# ManitoBoardv_7_1.net
KiCad netlist of a schematic drawn in EAGLE
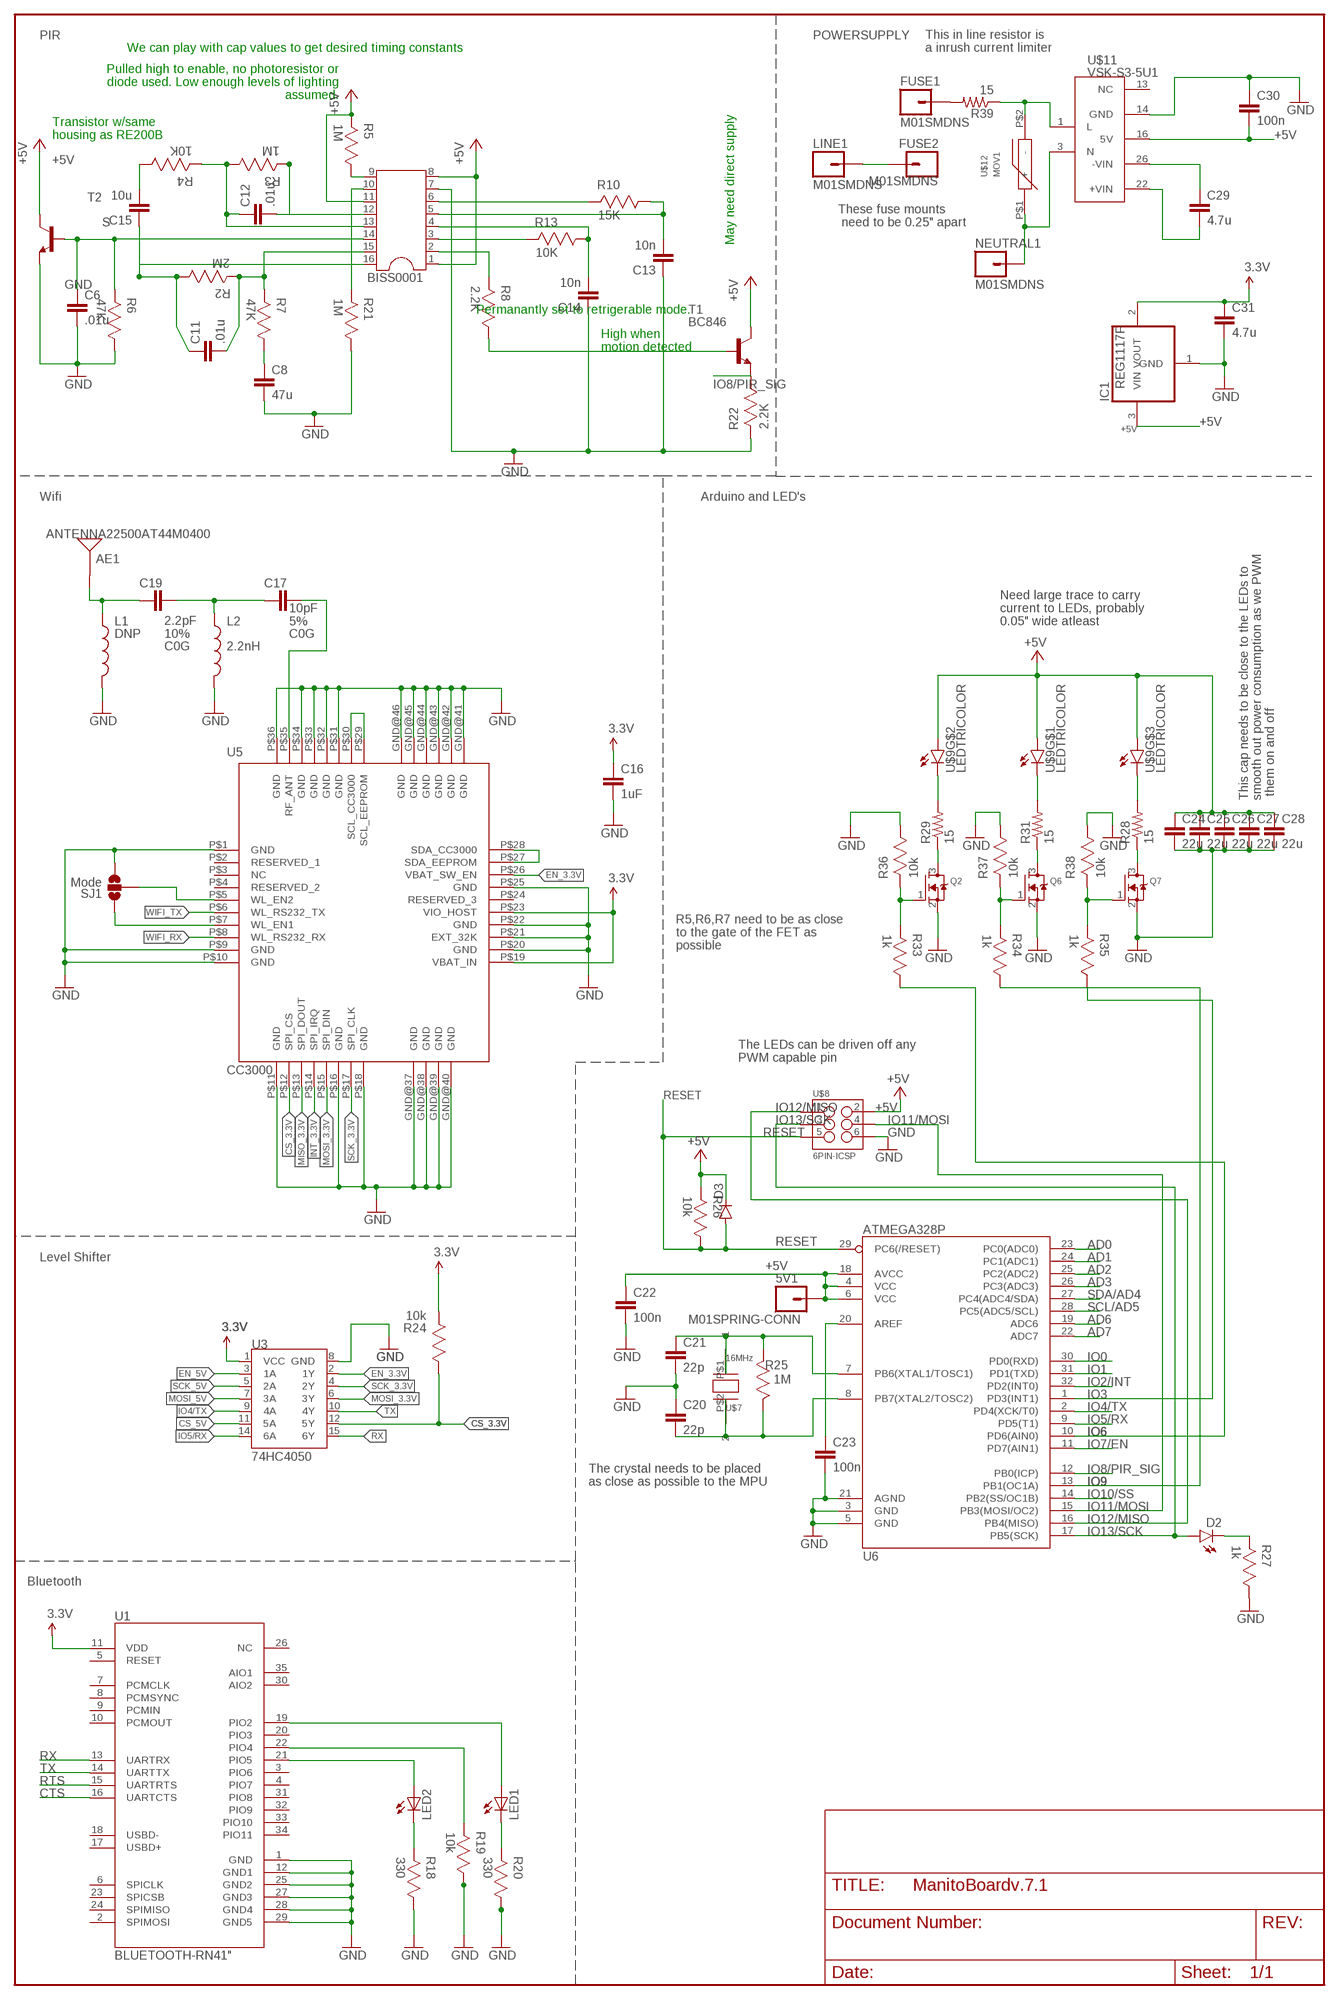
[diagram p0: schematic, sheet 1]

(export (version "E")
  (design (tool "Eeschema 10.0.6"))
  (components
    (comp (ref "5V1")
      (value "M01SPRING-CONN")
      (footprint "eagle-import:SPRING-CONNECTOR")
      (libsource (lib "eagle-import") (part "M01SPRING-CONN"))
    )
    (comp (ref "AE1")
      (value "ANTENNA22500AT44M0400")
      (footprint "eagle-import:ANTENNA-CHIP_2500AT44M0400")
      (libsource (lib "eagle-import") (part "ANTENNA22500AT44M0400"))
    )
    (comp (ref "BISS0001")
      (value "DIL16S")
      (footprint "eagle-import:SOCKET-16")
      (libsource (lib "eagle-import") (part "DIL16S"))
    )
    (comp (ref "C6")
      (value ".01u")
      (footprint "eagle-import:0805")
      (libsource (lib "eagle-import") (part "CAP0805"))
    )
    (comp (ref "C8")
      (value "47u")
      (footprint "eagle-import:0805")
      (libsource (lib "eagle-import") (part "CAP0805"))
    )
    (comp (ref "C11")
      (value ".01u")
      (footprint "eagle-import:0805")
      (libsource (lib "eagle-import") (part "CAP0805"))
    )
    (comp (ref "C12")
      (value ".01u")
      (footprint "eagle-import:0805")
      (libsource (lib "eagle-import") (part "CAP0805"))
    )
    (comp (ref "C13")
      (value "10n")
      (footprint "eagle-import:0805")
      (libsource (lib "eagle-import") (part "CAP0805"))
    )
    (comp (ref "C14")
      (value "10n")
      (footprint "eagle-import:0805")
      (libsource (lib "eagle-import") (part "CAP0805"))
    )
    (comp (ref "C15")
      (value "10u")
      (footprint "eagle-import:0805")
      (libsource (lib "eagle-import") (part "CAP0805"))
    )
    (comp (ref "C16")
      (value "1uF")
      (footprint "eagle-import:0805")
      (libsource (lib "eagle-import") (part "SparkFun-Capacitors_CAP0805"))
    )
    (comp (ref "C17")
      (value "10pF")
      (footprint "eagle-import:0603-CAP")
      (fields (field (name "COEFF") "C0G") (field (name "TOL") "5%"))
      (libsource (lib "eagle-import") (part "SparkFun-Capacitors_CAP0603-CAP"))
    )
    (comp (ref "C19")
      (value "2.2pF")
      (footprint "eagle-import:0603-CAP")
      (fields (field (name "COEFF") "C0G") (field (name "TOL") "10%"))
      (libsource (lib "eagle-import") (part "SparkFun-Capacitors_CAP0603-CAP"))
    )
    (comp (ref "C20")
      (value "22p")
      (footprint "eagle-import:0603-CAP")
      (libsource (lib "eagle-import") (part "CAP0603-CAP"))
    )
    (comp (ref "C21")
      (value "22p")
      (footprint "eagle-import:0603-CAP")
      (libsource (lib "eagle-import") (part "CAP0603-CAP"))
    )
    (comp (ref "C22")
      (value "100n")
      (footprint "eagle-import:0603-CAP")
      (libsource (lib "eagle-import") (part "CAP0603-CAP"))
    )
    (comp (ref "C23")
      (value "100n")
      (footprint "eagle-import:0603-CAP")
      (libsource (lib "eagle-import") (part "CAP0603-CAP"))
    )
    (comp (ref "C24")
      (value "22u")
      (footprint "eagle-import:0603-CAP")
      (libsource (lib "eagle-import") (part "CAP0603-CAP"))
    )
    (comp (ref "C25")
      (value "22u")
      (footprint "eagle-import:0603-CAP")
      (libsource (lib "eagle-import") (part "CAP0603-CAP"))
    )
    (comp (ref "C26")
      (value "22u")
      (footprint "eagle-import:0603-CAP")
      (libsource (lib "eagle-import") (part "CAP0603-CAP"))
    )
    (comp (ref "C27")
      (value "22u")
      (footprint "eagle-import:0603-CAP")
      (libsource (lib "eagle-import") (part "CAP0603-CAP"))
    )
    (comp (ref "C28")
      (value "22u")
      (footprint "eagle-import:0603-CAP")
      (libsource (lib "eagle-import") (part "CAP0603-CAP"))
    )
    (comp (ref "C29")
      (value "4.7u")
      (footprint "eagle-import:0603-CAP")
      (libsource (lib "eagle-import") (part "CAP0603-CAP"))
    )
    (comp (ref "C30")
      (value "100n")
      (footprint "eagle-import:0603-CAP")
      (libsource (lib "eagle-import") (part "CAP0603-CAP"))
    )
    (comp (ref "C31")
      (value "4.7u")
      (footprint "eagle-import:0603-CAP")
      (libsource (lib "eagle-import") (part "CAP0603-CAP"))
    )
    (comp (ref "D2")
      (value "LED-YELLOW0603")
      (footprint "eagle-import:LED-0603")
      (libsource (lib "eagle-import") (part "LED-YELLOW0603"))
    )
    (comp (ref "D3")
      (value "DIODE1N4148")
      (footprint "eagle-import:DIODE-1N4148")
      (libsource (lib "eagle-import") (part "DIODE1N4148"))
    )
    (comp (ref "FUSE1")
      (value "M01SMDNS")
      (footprint "eagle-import:1X01NS")
      (libsource (lib "eagle-import") (part "M01SMDNS"))
    )
    (comp (ref "FUSE2")
      (value "M01SMDNS")
      (footprint "eagle-import:1X01NS")
      (libsource (lib "eagle-import") (part "M01SMDNS"))
    )
    (comp (ref "IC1")
      (value "REG1117F")
      (footprint "eagle-import:DD-3")
      (fields (field (name "MF") "TEXAS INSTRUMENTS") (field (name "MPN") "REG1117FAKTTT"))
      (libsource (lib "eagle-import") (part "REG1117F"))
    )
    (comp (ref "L1")
      (value "DNP")
      (footprint "eagle-import:0603")
      (libsource (lib "eagle-import") (part "INDUCTOR0603"))
    )
    (comp (ref "L2")
      (value "2.2nH")
      (footprint "eagle-import:0603")
      (libsource (lib "eagle-import") (part "INDUCTOR0603"))
    )
    (comp (ref "LED1")
      (value "LED_ESML0603")
      (footprint "eagle-import:LED_SML0603")
      (libsource (lib "eagle-import") (part "LED_ESML0603"))
    )
    (comp (ref "LED2")
      (value "LED_ESML0603")
      (footprint "eagle-import:LED_SML0603")
      (libsource (lib "eagle-import") (part "LED_ESML0603"))
    )
    (comp (ref "LINE1")
      (value "M01SMDNS")
      (footprint "eagle-import:1X01NS")
      (libsource (lib "eagle-import") (part "M01SMDNS"))
    )
    (comp (ref "NEUTRAL1")
      (value "M01SMDNS")
      (footprint "eagle-import:1X01NS")
      (libsource (lib "eagle-import") (part "M01SMDNS"))
    )
    (comp (ref "Q2")
      (value "MOSFET-NREFLOW")
      (footprint "eagle-import:SOT23")
      (libsource (lib "eagle-import") (part "MOSFET-NREFLOW"))
    )
    (comp (ref "Q6")
      (value "MOSFET-NREFLOW")
      (footprint "eagle-import:SOT23")
      (libsource (lib "eagle-import") (part "MOSFET-NREFLOW"))
    )
    (comp (ref "Q7")
      (value "MOSFET-NREFLOW")
      (footprint "eagle-import:SOT23")
      (libsource (lib "eagle-import") (part "MOSFET-NREFLOW"))
    )
    (comp (ref "R2")
      (value "2M")
      (footprint "eagle-import:0603RESISTOR")
      (fields (field (name "MPN") "CRCW06031K21FKEA") (field (name "TOLERANCE") "± 1.0 %"))
      (libsource (lib "eagle-import") (part "0603RESISTOR1"))
    )
    (comp (ref "R3")
      (value "1M")
      (footprint "eagle-import:0603RESISTOR")
      (fields (field (name "MPN") "CRCW06031K21FKEA") (field (name "TOLERANCE") "± 1.0 %"))
      (libsource (lib "eagle-import") (part "0603RESISTOR1"))
    )
    (comp (ref "R4")
      (value "10K")
      (footprint "eagle-import:0603RESISTOR")
      (fields (field (name "MPN") "CRCW06031K21FKEA") (field (name "TOLERANCE") "± 1.0 %"))
      (libsource (lib "eagle-import") (part "0603RESISTOR1"))
    )
    (comp (ref "R5")
      (value "1M")
      (footprint "eagle-import:0603RESISTOR")
      (fields (field (name "MPN") "CRCW06031K21FKEA") (field (name "TOLERANCE") "± 1.0 %"))
      (libsource (lib "eagle-import") (part "0603RESISTOR1"))
    )
    (comp (ref "R6")
      (value "47K")
      (footprint "eagle-import:0603RESISTOR")
      (fields (field (name "MPN") "CRCW06031K21FKEA") (field (name "TOLERANCE") "± 1.0 %"))
      (libsource (lib "eagle-import") (part "0603RESISTOR1"))
    )
    (comp (ref "R7")
      (value "47K")
      (footprint "eagle-import:0603RESISTOR")
      (fields (field (name "MPN") "CRCW06031K21FKEA") (field (name "TOLERANCE") "± 1.0 %"))
      (libsource (lib "eagle-import") (part "0603RESISTOR1"))
    )
    (comp (ref "R8")
      (value "2.2K")
      (footprint "eagle-import:0603RESISTOR")
      (fields (field (name "MPN") "CRCW06031K21FKEA") (field (name "TOLERANCE") "± 1.0 %"))
      (libsource (lib "eagle-import") (part "0603RESISTOR1"))
    )
    (comp (ref "R10")
      (value "15K")
      (footprint "eagle-import:0603RESISTOR")
      (fields (field (name "MPN") "CRCW06031K21FKEA") (field (name "TOLERANCE") "± 1.0 %"))
      (libsource (lib "eagle-import") (part "0603RESISTOR1"))
    )
    (comp (ref "R13")
      (value "10K")
      (footprint "eagle-import:0603RESISTOR")
      (fields (field (name "MPN") "CRCW06031K21FKEA") (field (name "TOLERANCE") "± 1.0 %"))
      (libsource (lib "eagle-import") (part "0603RESISTOR1"))
    )
    (comp (ref "R18")
      (value "330")
      (footprint "eagle-import:0603RESISTOR")
      (fields (field (name "MPN") "CRCW06031K21FKEA") (field (name "TOLERANCE") "± 1.0 %"))
      (libsource (lib "eagle-import") (part "0603RESISTOR1"))
    )
    (comp (ref "R19")
      (value "10k")
      (footprint "eagle-import:0603RESISTOR")
      (fields (field (name "MPN") "CRCW06031K21FKEA") (field (name "TOLERANCE") "± 1.0 %"))
      (libsource (lib "eagle-import") (part "0603RESISTOR1"))
    )
    (comp (ref "R20")
      (value "330")
      (footprint "eagle-import:0603RESISTOR")
      (fields (field (name "MPN") "CRCW06031K21FKEA") (field (name "TOLERANCE") "± 1.0 %"))
      (libsource (lib "eagle-import") (part "0603RESISTOR1"))
    )
    (comp (ref "R21")
      (value "1M")
      (footprint "eagle-import:0603RESISTOR")
      (fields (field (name "MPN") "CRCW06031K21FKEA") (field (name "TOLERANCE") "± 1.0 %"))
      (libsource (lib "eagle-import") (part "0603RESISTOR1"))
    )
    (comp (ref "R22")
      (value "2.2K")
      (footprint "eagle-import:0603RESISTOR")
      (fields (field (name "MPN") "CRCW06031K21FKEA") (field (name "TOLERANCE") "± 1.0 %"))
      (libsource (lib "eagle-import") (part "0603RESISTOR1"))
    )
    (comp (ref "R24")
      (value "10k")
      (footprint "eagle-import:0603RESISTOR")
      (fields (field (name "MPN") "CRCW06031K21FKEA") (field (name "TOLERANCE") "± 1.0 %"))
      (libsource (lib "eagle-import") (part "0603RESISTOR1"))
    )
    (comp (ref "R25")
      (value "1M")
      (footprint "eagle-import:0603RESISTOR")
      (fields (field (name "MPN") "CRCW06031K21FKEA") (field (name "TOLERANCE") "± 1.0 %"))
      (libsource (lib "eagle-import") (part "0603RESISTOR1"))
    )
    (comp (ref "R26")
      (value "10k")
      (footprint "eagle-import:0603RESISTOR")
      (fields (field (name "MPN") "CRCW06031K21FKEA") (field (name "TOLERANCE") "± 1.0 %"))
      (libsource (lib "eagle-import") (part "0603RESISTOR1"))
    )
    (comp (ref "R27")
      (value "1k")
      (footprint "eagle-import:0603RESISTOR")
      (fields (field (name "MPN") "CRCW06031K21FKEA") (field (name "TOLERANCE") "± 1.0 %"))
      (libsource (lib "eagle-import") (part "0603RESISTOR1"))
    )
    (comp (ref "R28")
      (value "15")
      (footprint "eagle-import:AXIAL-0.6")
      (libsource (lib "eagle-import") (part "RESISTORPTH-1W"))
    )
    (comp (ref "R29")
      (value "15")
      (footprint "eagle-import:AXIAL-0.6")
      (libsource (lib "eagle-import") (part "RESISTORPTH-1W"))
    )
    (comp (ref "R31")
      (value "15")
      (footprint "eagle-import:AXIAL-0.6")
      (libsource (lib "eagle-import") (part "RESISTORPTH-1W"))
    )
    (comp (ref "R33")
      (value "1k")
      (footprint "eagle-import:0603RESISTOR")
      (fields (field (name "MPN") "CRCW06031K21FKEA") (field (name "TOLERANCE") "± 1.0 %"))
      (libsource (lib "eagle-import") (part "0603RESISTOR1"))
    )
    (comp (ref "R34")
      (value "1k")
      (footprint "eagle-import:0603RESISTOR")
      (fields (field (name "MPN") "CRCW06031K21FKEA") (field (name "TOLERANCE") "± 1.0 %"))
      (libsource (lib "eagle-import") (part "0603RESISTOR1"))
    )
    (comp (ref "R35")
      (value "1k")
      (footprint "eagle-import:0603RESISTOR")
      (fields (field (name "MPN") "CRCW06031K21FKEA") (field (name "TOLERANCE") "± 1.0 %"))
      (libsource (lib "eagle-import") (part "0603RESISTOR1"))
    )
    (comp (ref "R36")
      (value "10k")
      (footprint "eagle-import:0603RESISTOR")
      (fields (field (name "MPN") "CRCW06031K21FKEA") (field (name "TOLERANCE") "± 1.0 %"))
      (libsource (lib "eagle-import") (part "0603RESISTOR1"))
    )
    (comp (ref "R37")
      (value "10k")
      (footprint "eagle-import:0603RESISTOR")
      (fields (field (name "MPN") "CRCW06031K21FKEA") (field (name "TOLERANCE") "± 1.0 %"))
      (libsource (lib "eagle-import") (part "0603RESISTOR1"))
    )
    (comp (ref "R38")
      (value "10k")
      (footprint "eagle-import:0603RESISTOR")
      (fields (field (name "MPN") "CRCW06031K21FKEA") (field (name "TOLERANCE") "± 1.0 %"))
      (libsource (lib "eagle-import") (part "0603RESISTOR1"))
    )
    (comp (ref "R39")
      (value "15")
      (footprint "eagle-import:AXIAL-0.6")
      (libsource (lib "eagle-import") (part "RESISTORPTH-1W"))
    )
    (comp (ref "SJ1")
      (value "Mode")
      (footprint "eagle-import:SJ_3_PASTE1&2")
      (libsource (lib "eagle-import") (part "SOLDERJUMPER_2WAYPASTE1&2"))
    )
    (comp (ref "T1")
      (value "BC846")
      (footprint "eagle-import:SOT23")
      (libsource (lib "eagle-import") (part "BC846"))
    )
    (comp (ref "T2")
      (value "-NPN-TO5")
      (footprint "eagle-import:TO5")
      (libsource (lib "eagle-import") (part "-NPN-TO5"))
    )
    (comp (ref "U$7")
      (value "16MHz")
      (footprint "eagle-import:SMDCRYSTAL")
      (libsource (lib "eagle-import") (part "SMDCRYSTAL"))
    )
    (comp (ref "U$8")
      (value "6PIN-ICSP")
      (footprint "eagle-import:2X3-ICSP")
      (libsource (lib "eagle-import") (part "6PIN-ICSP"))
    )
    (comp (ref "U$9")
      (value "LEDTRICOLOR")
      (footprint "eagle-import:TRICOLORLED")
      (libsource (lib "eagle-import") (part "LEDTRICOLOR"))
    )
    (comp (ref "U$11")
      (value "VSK-S3-5U1")
      (footprint "eagle-import:VSK-S3-DCAC")
      (libsource (lib "eagle-import") (part "VSK-S3-5U1"))
    )
    (comp (ref "U$12")
      (value "MOV1")
      (footprint "eagle-import:MOV")
      (libsource (lib "eagle-import") (part "MOV1"))
    )
    (comp (ref "U1")
      (value "BLUETOOTH-RN41\"")
      (footprint "eagle-import:RN41")
      (libsource (lib "eagle-import") (part "BLUETOOTH-RN41{dblquote}"))
    )
    (comp (ref "U3")
      (value "74HC4050")
      (footprint "eagle-import:SO016")
      (libsource (lib "eagle-import") (part "HEX_CONVERTER"))
    )
    (comp (ref "U5")
      (value "CC3000")
      (footprint "eagle-import:QFN-46_CC3000")
      (libsource (lib "eagle-import") (part "CC3000"))
    )
    (comp (ref "U6")
      (value "ATMEGA328P")
      (footprint "eagle-import:TQFP32-08")
      (libsource (lib "eagle-import") (part "ATMEGA328_SMT"))
    )
  )
  (nets
    (net (code "1") (name "+5V") (class "Default")
      (node (ref "5V1") (pin "P$2") (pinfunction "1_P$2") (pintype "passive"))
      (node (ref "BISS0001") (pin "1") (pinfunction "1_1") (pintype "passive"))
      (node (ref "BISS0001") (pin "11") (pinfunction "11_11") (pintype "passive"))
      (node (ref "BISS0001") (pin "8") (pinfunction "8_8") (pintype "passive"))
      (node (ref "C22") (pin "1") (pinfunction "1_1") (pintype "passive"))
      (node (ref "C24") (pin "1") (pinfunction "1_1") (pintype "passive"))
      (node (ref "C25") (pin "1") (pinfunction "1_1") (pintype "passive"))
      (node (ref "C26") (pin "1") (pinfunction "1_1") (pintype "passive"))
      (node (ref "C27") (pin "1") (pinfunction "1_1") (pintype "passive"))
      (node (ref "C28") (pin "1") (pinfunction "1_1") (pintype "passive"))
      (node (ref "C30") (pin "2") (pinfunction "2_2") (pintype "passive"))
      (node (ref "D3") (pin "C") (pinfunction "C_C") (pintype "passive"))
      (node (ref "IC1") (pin "3") (pinfunction "VIN_3") (pintype "input"))
      (node (ref "R26") (pin "2") (pinfunction "2_2") (pintype "passive"))
      (node (ref "R5") (pin "2") (pinfunction "2_2") (pintype "passive"))
      (node (ref "T1") (pin "3") (pinfunction "C_3") (pintype "passive"))
      (node (ref "T2") (pin "3") (pinfunction "C_3") (pintype "passive"))
      (node (ref "U$11") (pin "16") (pinfunction "5V_16") (pintype "bidirectional"))
      (node (ref "U$8") (pin "2") (pinfunction "+5V_2") (pintype "power_in"))
      (node (ref "U$9") (pin "A1") (pinfunction "A_A1") (pintype "passive"))
      (node (ref "U$9") (pin "A2") (pinfunction "A_A2") (pintype "passive"))
      (node (ref "U$9") (pin "A3") (pinfunction "A_A3") (pintype "passive"))
      (node (ref "U6") (pin "18") (pinfunction "AVCC_18") (pintype "bidirectional"))
      (node (ref "U6") (pin "4") (pinfunction "VCC_4") (pintype "bidirectional"))
      (node (ref "U6") (pin "6") (pinfunction "VCC_6") (pintype "bidirectional"))
    )
    (net (code "2") (name "/AD0") (class "Default")
      (node (ref "U6") (pin "23") (pinfunction "PC0(ADC0)_23") (pintype "bidirectional"))
    )
    (net (code "3") (name "/AD1") (class "Default")
      (node (ref "U6") (pin "24") (pinfunction "PC1(ADC1)_24") (pintype "bidirectional"))
    )
    (net (code "4") (name "/AD2") (class "Default")
      (node (ref "U6") (pin "25") (pinfunction "PC2(ADC2)_25") (pintype "bidirectional"))
    )
    (net (code "5") (name "/AD3") (class "Default")
      (node (ref "U6") (pin "26") (pinfunction "PC3(ADC3)_26") (pintype "bidirectional"))
    )
    (net (code "6") (name "/AD6") (class "Default")
      (node (ref "U6") (pin "19") (pinfunction "ADC6_19") (pintype "bidirectional"))
    )
    (net (code "7") (name "/AD7") (class "Default")
      (node (ref "U6") (pin "22") (pinfunction "ADC7_22") (pintype "bidirectional"))
    )
    (net (code "8") (name "/CTS") (class "Default")
      (node (ref "U1") (pin "16") (pinfunction "UARTCTS_16") (pintype "bidirectional"))
    )
    (net (code "9") (name "/IO0") (class "Default")
      (node (ref "U6") (pin "30") (pinfunction "PD0(RXD)_30") (pintype "bidirectional"))
    )
    (net (code "10") (name "/IO1") (class "Default")
      (node (ref "U6") (pin "31") (pinfunction "PD1(TXD)_31") (pintype "bidirectional"))
    )
    (net (code "11") (name "/IO2{slash}INT") (class "Default")
      (node (ref "U6") (pin "32") (pinfunction "PD2(INT0)_32") (pintype "bidirectional"))
    )
    (net (code "12") (name "/IO3") (class "Default")
      (node (ref "R35") (pin "1") (pinfunction "1_1") (pintype "passive"))
      (node (ref "U6") (pin "1") (pinfunction "PD3(INT1)_1") (pintype "bidirectional"))
    )
    (net (code "13") (name "/IO6") (class "Default")
      (node (ref "R33") (pin "1") (pinfunction "1_1") (pintype "passive"))
      (node (ref "U6") (pin "10") (pinfunction "PD6(AIN0)_10") (pintype "bidirectional"))
    )
    (net (code "14") (name "/IO7{slash}EN") (class "Default")
      (node (ref "U6") (pin "11") (pinfunction "PD7(AIN1)_11") (pintype "bidirectional"))
    )
    (net (code "15") (name "/IO8{slash}PIR_SIG") (class "Default")
      (node (ref "R22") (pin "1") (pinfunction "1_1") (pintype "passive"))
      (node (ref "T1") (pin "2") (pinfunction "E_2") (pintype "passive"))
      (node (ref "U6") (pin "12") (pinfunction "PB0(ICP)_12") (pintype "bidirectional"))
    )
    (net (code "16") (name "/IO9") (class "Default")
      (node (ref "R34") (pin "1") (pinfunction "1_1") (pintype "passive"))
      (node (ref "U6") (pin "13") (pinfunction "PB1(OC1A)_13") (pintype "bidirectional"))
    )
    (net (code "17") (name "/IO10{slash}SS") (class "Default")
      (node (ref "U6") (pin "14") (pinfunction "PB2(SS/OC1B)_14") (pintype "bidirectional"))
    )
    (net (code "18") (name "/IO11{slash}MOSI") (class "Default")
      (node (ref "U$8") (pin "4") (pinfunction "MOSI_4") (pintype "bidirectional"))
      (node (ref "U6") (pin "15") (pinfunction "PB3(MOSI/OC2)_15") (pintype "bidirectional"))
    )
    (net (code "19") (name "/IO12{slash}MISO") (class "Default")
      (node (ref "U$8") (pin "1") (pinfunction "MISO_1") (pintype "bidirectional"))
      (node (ref "U6") (pin "16") (pinfunction "PB4(MISO)_16") (pintype "bidirectional"))
    )
    (net (code "20") (name "/IO13{slash}SCK") (class "Default")
      (node (ref "D2") (pin "A") (pinfunction "A_A") (pintype "passive"))
      (node (ref "U$8") (pin "3") (pinfunction "SCK_3") (pintype "bidirectional"))
      (node (ref "U6") (pin "17") (pinfunction "PB5(SCK)_17") (pintype "bidirectional"))
    )
    (net (code "22") (name "/RESET") (class "Default")
      (node (ref "D3") (pin "A") (pinfunction "A_A") (pintype "passive"))
      (node (ref "R26") (pin "1") (pinfunction "1_1") (pintype "passive"))
      (node (ref "U$8") (pin "5") (pinfunction "RESET_5") (pintype "bidirectional"))
      (node (ref "U6") (pin "29") (pinfunction "PC6(/RESET)_29") (pintype "bidirectional"))
    )
    (net (code "23") (name "/RTS") (class "Default")
      (node (ref "U1") (pin "15") (pinfunction "UARTRTS_15") (pintype "bidirectional"))
    )
    (net (code "24") (name "/S") (class "Default")
      (node (ref "BISS0001") (pin "14") (pinfunction "14_14") (pintype "passive"))
      (node (ref "C6") (pin "1") (pinfunction "1_1") (pintype "passive"))
      (node (ref "R6") (pin "2") (pinfunction "2_2") (pintype "passive"))
      (node (ref "T2") (pin "2") (pinfunction "B_2") (pintype "passive"))
    )
    (net (code "25") (name "/SCL{slash}AD5") (class "Default")
      (node (ref "U6") (pin "28") (pinfunction "PC5(ADC5/SCL)_28") (pintype "bidirectional"))
    )
    (net (code "26") (name "/SDA{slash}AD4") (class "Default")
      (node (ref "U6") (pin "27") (pinfunction "PC4(ADC4/SDA)_27") (pintype "bidirectional"))
    )
    (net (code "27") (name "3.3V") (class "Default")
      (node (ref "C16") (pin "1") (pinfunction "1_1") (pintype "passive"))
      (node (ref "C31") (pin "1") (pinfunction "1_1") (pintype "passive"))
      (node (ref "IC1") (pin "2") (pinfunction "VOUT_2") (pintype "output"))
      (node (ref "R24") (pin "2") (pinfunction "2_2") (pintype "passive"))
      (node (ref "U1") (pin "11") (pinfunction "VDD_11") (pintype "bidirectional"))
      (node (ref "U3") (pin "1") (pinfunction "VCC_1") (pintype "bidirectional"))
      (node (ref "U5") (pin "P$19") (pinfunction "VBAT_IN_P$19") (pintype "bidirectional"))
      (node (ref "U5") (pin "P$23") (pinfunction "VIO_HOST_P$23") (pintype "bidirectional"))
    )
    (net (code "28") (name "CS_3.3V") (class "Default")
      (node (ref "R24") (pin "1") (pinfunction "1_1") (pintype "passive"))
      (node (ref "U3") (pin "12") (pinfunction "5Y_12") (pintype "bidirectional"))
      (node (ref "U5") (pin "P$12") (pinfunction "SPI_CS_P$12") (pintype "bidirectional"))
    )
    (net (code "29") (name "CS_5V") (class "Default")
      (node (ref "U3") (pin "11") (pinfunction "5A_11") (pintype "bidirectional"))
    )
    (net (code "30") (name "EN_3.3V") (class "Default")
      (node (ref "U3") (pin "2") (pinfunction "1Y_2") (pintype "bidirectional"))
      (node (ref "U5") (pin "P$26") (pinfunction "VBAT_SW_EN_P$26") (pintype "bidirectional"))
    )
    (net (code "31") (name "EN_5V") (class "Default")
      (node (ref "U3") (pin "3") (pinfunction "1A_3") (pintype "bidirectional"))
    )
    (net (code "32") (name "GND") (class "Default")
      (node (ref "BISS0001") (pin "7") (pinfunction "7_7") (pintype "passive"))
      (node (ref "C13") (pin "1") (pinfunction "1_1") (pintype "passive"))
      (node (ref "C14") (pin "1") (pinfunction "1_1") (pintype "passive"))
      (node (ref "C16") (pin "2") (pinfunction "2_2") (pintype "passive"))
      (node (ref "C20") (pin "1") (pinfunction "1_1") (pintype "passive"))
      (node (ref "C21") (pin "2") (pinfunction "2_2") (pintype "passive"))
      (node (ref "C22") (pin "2") (pinfunction "2_2") (pintype "passive"))
      (node (ref "C23") (pin "2") (pinfunction "2_2") (pintype "passive"))
      (node (ref "C24") (pin "2") (pinfunction "2_2") (pintype "passive"))
      (node (ref "C25") (pin "2") (pinfunction "2_2") (pintype "passive"))
      (node (ref "C26") (pin "2") (pinfunction "2_2") (pintype "passive"))
      (node (ref "C27") (pin "2") (pinfunction "2_2") (pintype "passive"))
      (node (ref "C28") (pin "2") (pinfunction "2_2") (pintype "passive"))
      (node (ref "C30") (pin "1") (pinfunction "1_1") (pintype "passive"))
      (node (ref "C31") (pin "2") (pinfunction "2_2") (pintype "passive"))
      (node (ref "C6") (pin "2") (pinfunction "2_2") (pintype "passive"))
      (node (ref "C8") (pin "2") (pinfunction "2_2") (pintype "passive"))
      (node (ref "IC1") (pin "1") (pinfunction "GND_1") (pintype "power_in"))
      (node (ref "L1") (pin "2") (pinfunction "2_2") (pintype "passive"))
      (node (ref "L2") (pin "2") (pinfunction "2_2") (pintype "passive"))
      (node (ref "Q2") (pin "2") (pinfunction "S_2") (pintype "bidirectional"))
      (node (ref "Q6") (pin "2") (pinfunction "S_2") (pintype "bidirectional"))
      (node (ref "Q7") (pin "2") (pinfunction "S_2") (pintype "bidirectional"))
      (node (ref "R18") (pin "1") (pinfunction "1_1") (pintype "passive"))
      (node (ref "R19") (pin "1") (pinfunction "1_1") (pintype "passive"))
      (node (ref "R20") (pin "1") (pinfunction "1_1") (pintype "passive"))
      (node (ref "R21") (pin "1") (pinfunction "1_1") (pintype "passive"))
      (node (ref "R22") (pin "2") (pinfunction "2_2") (pintype "passive"))
      (node (ref "R27") (pin "1") (pinfunction "1_1") (pintype "passive"))
      (node (ref "R36") (pin "1") (pinfunction "1_1") (pintype "passive"))
      (node (ref "R37") (pin "1") (pinfunction "1_1") (pintype "passive"))
      (node (ref "R38") (pin "1") (pinfunction "1_1") (pintype "passive"))
      (node (ref "R6") (pin "1") (pinfunction "1_1") (pintype "passive"))
      (node (ref "SJ1") (pin "3") (pinfunction "3_3") (pintype "passive"))
      (node (ref "T2") (pin "1") (pinfunction "E_1") (pintype "passive"))
      (node (ref "U$11") (pin "14") (pinfunction "GND_14") (pintype "bidirectional"))
      (node (ref "U$8") (pin "6") (pinfunction "GND_6") (pintype "power_in"))
      (node (ref "U1") (pin "1") (pinfunction "GND_1") (pintype "bidirectional"))
      (node (ref "U1") (pin "12") (pinfunction "GND1_12") (pintype "bidirectional"))
      (node (ref "U1") (pin "25") (pinfunction "GND2_25") (pintype "bidirectional"))
      (node (ref "U1") (pin "27") (pinfunction "GND3_27") (pintype "bidirectional"))
      (node (ref "U1") (pin "28") (pinfunction "GND4_28") (pintype "bidirectional"))
      (node (ref "U1") (pin "29") (pinfunction "GND5_29") (pintype "bidirectional"))
      (node (ref "U3") (pin "8") (pinfunction "GND_8") (pintype "bidirectional"))
      (node (ref "U5") (pin "GND@37") (pinfunction "GND_GND@37") (pintype "bidirectional"))
      (node (ref "U5") (pin "GND@38") (pinfunction "GND_GND@38") (pintype "bidirectional"))
      (node (ref "U5") (pin "GND@39") (pinfunction "GND_GND@39") (pintype "bidirectional"))
      (node (ref "U5") (pin "GND@40") (pinfunction "GND_GND@40") (pintype "bidirectional"))
      (node (ref "U5") (pin "GND@41") (pinfunction "GND_GND@41") (pintype "bidirectional"))
      (node (ref "U5") (pin "GND@42") (pinfunction "GND_GND@42") (pintype "bidirectional"))
      (node (ref "U5") (pin "GND@43") (pinfunction "GND_GND@43") (pintype "bidirectional"))
      (node (ref "U5") (pin "GND@44") (pinfunction "GND_GND@44") (pintype "bidirectional"))
      (node (ref "U5") (pin "GND@45") (pinfunction "GND_GND@45") (pintype "bidirectional"))
      (node (ref "U5") (pin "GND@46") (pinfunction "GND_GND@46") (pintype "bidirectional"))
      (node (ref "U5") (pin "P$1") (pinfunction "GND_P$1") (pintype "bidirectional"))
      (node (ref "U5") (pin "P$10") (pinfunction "GND_P$10") (pintype "bidirectional"))
      (node (ref "U5") (pin "P$11") (pinfunction "GND_P$11") (pintype "bidirectional"))
      (node (ref "U5") (pin "P$16") (pinfunction "GND_P$16") (pintype "bidirectional"))
      (node (ref "U5") (pin "P$18") (pinfunction "GND_P$18") (pintype "bidirectional"))
      (node (ref "U5") (pin "P$20") (pinfunction "GND_P$20") (pintype "bidirectional"))
      (node (ref "U5") (pin "P$21") (pinfunction "EXT_32K_P$21") (pintype "bidirectional"))
      (node (ref "U5") (pin "P$22") (pinfunction "GND_P$22") (pintype "bidirectional"))
      (node (ref "U5") (pin "P$25") (pinfunction "GND_P$25") (pintype "bidirectional"))
      (node (ref "U5") (pin "P$31") (pinfunction "GND_P$31") (pintype "bidirectional"))
      (node (ref "U5") (pin "P$32") (pinfunction "GND_P$32") (pintype "bidirectional"))
      (node (ref "U5") (pin "P$33") (pinfunction "GND_P$33") (pintype "bidirectional"))
      (node (ref "U5") (pin "P$34") (pinfunction "GND_P$34") (pintype "bidirectional"))
      (node (ref "U5") (pin "P$36") (pinfunction "GND_P$36") (pintype "bidirectional"))
      (node (ref "U5") (pin "P$9") (pinfunction "GND_P$9") (pintype "bidirectional"))
      (node (ref "U6") (pin "21") (pinfunction "AGND_21") (pintype "bidirectional"))
      (node (ref "U6") (pin "3") (pinfunction "GND_3") (pintype "bidirectional"))
      (node (ref "U6") (pin "5") (pinfunction "GND_5") (pintype "bidirectional"))
    )
    (net (code "33") (name "INT_3.3V") (class "Default")
      (node (ref "U5") (pin "P$14") (pinfunction "SPI_IRQ_P$14") (pintype "bidirectional"))
    )
    (net (code "34") (name "IO4{slash}TX") (class "Default")
      (node (ref "U3") (pin "9") (pinfunction "4A_9") (pintype "bidirectional"))
      (node (ref "U6") (pin "2") (pinfunction "PD4(XCK/T0)_2") (pintype "bidirectional"))
    )
    (net (code "35") (name "IO5{slash}RX") (class "Default")
      (node (ref "U3") (pin "14") (pinfunction "6A_14") (pintype "bidirectional"))
      (node (ref "U6") (pin "9") (pinfunction "PD5(T1)_9") (pintype "bidirectional"))
    )
    (net (code "36") (name "MISO_3.3V") (class "Default")
      (node (ref "U5") (pin "P$13") (pinfunction "SPI_DOUT_P$13") (pintype "bidirectional"))
    )
    (net (code "37") (name "MOSI_3.3V") (class "Default")
      (node (ref "U3") (pin "6") (pinfunction "3Y_6") (pintype "bidirectional"))
      (node (ref "U5") (pin "P$15") (pinfunction "SPI_DIN_P$15") (pintype "bidirectional"))
    )
    (net (code "38") (name "MOSI_5V") (class "Default")
      (node (ref "U3") (pin "7") (pinfunction "3A_7") (pintype "bidirectional"))
    )
    (net (code "39") (name "Net-(AE1-SIGNAL)") (class "Default")
      (node (ref "AE1") (pin "FEED") (pinfunction "SIGNAL_FEED") (pintype "bidirectional"))
      (node (ref "C19") (pin "1") (pinfunction "1_1") (pintype "passive"))
      (node (ref "L1") (pin "1") (pinfunction "1_1") (pintype "passive"))
    )
    (net (code "40") (name "Net-(BISS0001-Pad2)") (class "Default")
      (node (ref "BISS0001") (pin "2") (pinfunction "2_2") (pintype "passive"))
      (node (ref "R8") (pin "2") (pinfunction "2_2") (pintype "passive"))
    )
    (net (code "41") (name "Net-(BISS0001-Pad3)") (class "Default")
      (node (ref "BISS0001") (pin "3") (pinfunction "3_3") (pintype "passive"))
      (node (ref "R13") (pin "2") (pinfunction "2_2") (pintype "passive"))
    )
    (net (code "42") (name "Net-(BISS0001-Pad4)") (class "Default")
      (node (ref "BISS0001") (pin "4") (pinfunction "4_4") (pintype "passive"))
      (node (ref "C14") (pin "2") (pinfunction "2_2") (pintype "passive"))
      (node (ref "R13") (pin "1") (pinfunction "1_1") (pintype "passive"))
    )
    (net (code "43") (name "Net-(BISS0001-Pad5)") (class "Default")
      (node (ref "BISS0001") (pin "5") (pinfunction "5_5") (pintype "passive"))
      (node (ref "C13") (pin "2") (pinfunction "2_2") (pintype "passive"))
      (node (ref "R10") (pin "1") (pinfunction "1_1") (pintype "passive"))
    )
    (net (code "44") (name "Net-(BISS0001-Pad6)") (class "Default")
      (node (ref "BISS0001") (pin "6") (pinfunction "6_6") (pintype "passive"))
      (node (ref "R10") (pin "2") (pinfunction "2_2") (pintype "passive"))
    )
    (net (code "45") (name "Net-(BISS0001-Pad9)") (class "Default")
      (node (ref "BISS0001") (pin "9") (pinfunction "9_9") (pintype "passive"))
      (node (ref "R5") (pin "1") (pinfunction "1_1") (pintype "passive"))
    )
    (net (code "46") (name "Net-(BISS0001-Pad10)") (class "Default")
      (node (ref "BISS0001") (pin "10") (pinfunction "10_10") (pintype "passive"))
      (node (ref "R21") (pin "2") (pinfunction "2_2") (pintype "passive"))
    )
    (net (code "47") (name "Net-(BISS0001-Pad12)") (class "Default")
      (node (ref "BISS0001") (pin "12") (pinfunction "12_12") (pintype "passive"))
      (node (ref "C12") (pin "2") (pinfunction "2_2") (pintype "passive"))
      (node (ref "R3") (pin "2") (pinfunction "2_2") (pintype "passive"))
    )
    (net (code "48") (name "Net-(BISS0001-Pad13)") (class "Default")
      (node (ref "BISS0001") (pin "13") (pinfunction "13_13") (pintype "passive"))
      (node (ref "C12") (pin "1") (pinfunction "1_1") (pintype "passive"))
      (node (ref "R3") (pin "1") (pinfunction "1_1") (pintype "passive"))
      (node (ref "R4") (pin "2") (pinfunction "2_2") (pintype "passive"))
    )
    (net (code "49") (name "Net-(BISS0001-Pad15)") (class "Default")
      (node (ref "BISS0001") (pin "15") (pinfunction "15_15") (pintype "passive"))
      (node (ref "C11") (pin "2") (pinfunction "2_2") (pintype "passive"))
      (node (ref "R2") (pin "2") (pinfunction "2_2") (pintype "passive"))
      (node (ref "R7") (pin "2") (pinfunction "2_2") (pintype "passive"))
    )
    (net (code "50") (name "Net-(BISS0001-Pad16)") (class "Default")
      (node (ref "BISS0001") (pin "16") (pinfunction "16_16") (pintype "passive"))
      (node (ref "C11") (pin "1") (pinfunction "1_1") (pintype "passive"))
      (node (ref "C15") (pin "1") (pinfunction "1_1") (pintype "passive"))
      (node (ref "R2") (pin "1") (pinfunction "1_1") (pintype "passive"))
    )
    (net (code "51") (name "Net-(C8-Pad1)") (class "Default")
      (node (ref "C8") (pin "1") (pinfunction "1_1") (pintype "passive"))
      (node (ref "R7") (pin "1") (pinfunction "1_1") (pintype "passive"))
    )
    (net (code "52") (name "Net-(C15-Pad2)") (class "Default")
      (node (ref "C15") (pin "2") (pinfunction "2_2") (pintype "passive"))
      (node (ref "R4") (pin "1") (pinfunction "1_1") (pintype "passive"))
    )
    (net (code "53") (name "Net-(C17-Pad1)") (class "Default")
      (node (ref "C17") (pin "1") (pinfunction "1_1") (pintype "passive"))
      (node (ref "C19") (pin "2") (pinfunction "2_2") (pintype "passive"))
      (node (ref "L2") (pin "1") (pinfunction "1_1") (pintype "passive"))
    )
    (net (code "54") (name "Net-(D2-PadC)") (class "Default")
      (node (ref "D2") (pin "C") (pinfunction "C_C") (pintype "passive"))
      (node (ref "R27") (pin "2") (pinfunction "2_2") (pintype "passive"))
    )
    (net (code "55") (name "Net-(FUSE2-Pad1)") (class "Default")
      (node (ref "FUSE2") (pin "1") (pinfunction "1_1") (pintype "passive"))
      (node (ref "LINE1") (pin "1") (pinfunction "1_1") (pintype "passive"))
    )
    (net (code "56") (name "Net-(LED1-PadC)") (class "Default")
      (node (ref "LED1") (pin "C") (pinfunction "C_C") (pintype "passive"))
      (node (ref "R20") (pin "2") (pinfunction "2_2") (pintype "passive"))
    )
    (net (code "57") (name "Net-(LED2-PadC)") (class "Default")
      (node (ref "LED2") (pin "C") (pinfunction "C_C") (pintype "passive"))
      (node (ref "R18") (pin "2") (pinfunction "2_2") (pintype "passive"))
    )
    (net (code "58") (name "Net-(Q2-D)") (class "Default")
      (node (ref "Q2") (pin "3") (pinfunction "D_3") (pintype "bidirectional"))
      (node (ref "R29") (pin "P$1") (pinfunction "1_P$1") (pintype "passive"))
    )
    (net (code "59") (name "Net-(Q2-G)") (class "Default")
      (node (ref "Q2") (pin "1") (pinfunction "G_1") (pintype "bidirectional"))
      (node (ref "R33") (pin "2") (pinfunction "2_2") (pintype "passive"))
      (node (ref "R36") (pin "2") (pinfunction "2_2") (pintype "passive"))
    )
    (net (code "60") (name "Net-(Q6-D)") (class "Default")
      (node (ref "Q6") (pin "3") (pinfunction "D_3") (pintype "bidirectional"))
      (node (ref "R31") (pin "P$1") (pinfunction "1_P$1") (pintype "passive"))
    )
    (net (code "61") (name "Net-(Q6-G)") (class "Default")
      (node (ref "Q6") (pin "1") (pinfunction "G_1") (pintype "bidirectional"))
      (node (ref "R34") (pin "2") (pinfunction "2_2") (pintype "passive"))
      (node (ref "R37") (pin "2") (pinfunction "2_2") (pintype "passive"))
    )
    (net (code "62") (name "Net-(Q7-D)") (class "Default")
      (node (ref "Q7") (pin "3") (pinfunction "D_3") (pintype "bidirectional"))
      (node (ref "R28") (pin "P$1") (pinfunction "1_P$1") (pintype "passive"))
    )
    (net (code "63") (name "Net-(Q7-G)") (class "Default")
      (node (ref "Q7") (pin "1") (pinfunction "G_1") (pintype "bidirectional"))
      (node (ref "R35") (pin "2") (pinfunction "2_2") (pintype "passive"))
      (node (ref "R38") (pin "2") (pinfunction "2_2") (pintype "passive"))
    )
    (net (code "64") (name "Net-(R28-2)") (class "Default")
      (node (ref "R28") (pin "P$2") (pinfunction "2_P$2") (pintype "passive"))
      (node (ref "U$9") (pin "C3") (pinfunction "C_C3") (pintype "passive"))
    )
    (net (code "65") (name "Net-(R29-2)") (class "Default")
      (node (ref "R29") (pin "P$2") (pinfunction "2_P$2") (pintype "passive"))
      (node (ref "U$9") (pin "C2") (pinfunction "C_C2") (pintype "passive"))
    )
    (net (code "66") (name "Net-(R31-2)") (class "Default")
      (node (ref "R31") (pin "P$2") (pinfunction "2_P$2") (pintype "passive"))
      (node (ref "U$9") (pin "C1") (pinfunction "C_C1") (pintype "passive"))
    )
    (net (code "67") (name "Net-(R39-1)") (class "Default")
      (node (ref "R39") (pin "P$1") (pinfunction "1_P$1") (pintype "passive"))
      (node (ref "U$11") (pin "1") (pinfunction "L_1") (pintype "bidirectional"))
      (node (ref "U$12") (pin "P$2") (pinfunction "-_P$2") (pintype "bidirectional"))
    )
    (net (code "68") (name "Net-(R39-2)") (class "Default")
      (node (ref "FUSE1") (pin "1") (pinfunction "1_1") (pintype "passive"))
      (node (ref "R39") (pin "P$2") (pinfunction "2_P$2") (pintype "passive"))
    )
    (net (code "69") (name "Net-(T1-B)") (class "Default")
      (node (ref "R8") (pin "1") (pinfunction "1_1") (pintype "passive"))
      (node (ref "T1") (pin "1") (pinfunction "B_1") (pintype "passive"))
    )
    (net (code "70") (name "Net-(U$7-1)") (class "Default")
      (node (ref "C21") (pin "1") (pinfunction "1_1") (pintype "passive"))
      (node (ref "R25") (pin "2") (pinfunction "2_2") (pintype "passive"))
      (node (ref "U$7") (pin "P$1") (pinfunction "1_P$1") (pintype "bidirectional"))
      (node (ref "U6") (pin "7") (pinfunction "PB6(XTAL1/TOSC1)_7") (pintype "bidirectional"))
    )
    (net (code "71") (name "Net-(U$7-2)") (class "Default")
      (node (ref "C20") (pin "2") (pinfunction "2_2") (pintype "passive"))
      (node (ref "R25") (pin "1") (pinfunction "1_1") (pintype "passive"))
      (node (ref "U$7") (pin "P$2") (pinfunction "2_P$2") (pintype "bidirectional"))
      (node (ref "U6") (pin "8") (pinfunction "PB7(XTAL2/TOSC2)_8") (pintype "bidirectional"))
    )
    (net (code "72") (name "Net-(U$11-+VIN)") (class "Default")
      (node (ref "C29") (pin "2") (pinfunction "2_2") (pintype "passive"))
      (node (ref "U$11") (pin "22") (pinfunction "+VIN_22") (pintype "bidirectional"))
    )
    (net (code "73") (name "Net-(U$11--VIN)") (class "Default")
      (node (ref "C29") (pin "1") (pinfunction "1_1") (pintype "passive"))
      (node (ref "U$11") (pin "26") (pinfunction "-VIN_26") (pintype "bidirectional"))
    )
    (net (code "74") (name "Net-(U$11-N)") (class "Default")
      (node (ref "NEUTRAL1") (pin "1") (pinfunction "1_1") (pintype "passive"))
      (node (ref "U$11") (pin "3") (pinfunction "N_3") (pintype "bidirectional"))
      (node (ref "U$12") (pin "P$1") (pinfunction "+_P$1") (pintype "bidirectional"))
    )
    (net (code "75") (name "Net-(U1-PIO2)") (class "Default")
      (node (ref "LED1") (pin "A") (pinfunction "A_A") (pintype "passive"))
      (node (ref "U1") (pin "19") (pinfunction "PIO2_19") (pintype "bidirectional"))
    )
    (net (code "76") (name "Net-(U1-PIO4)") (class "Default")
      (node (ref "R19") (pin "2") (pinfunction "2_2") (pintype "passive"))
      (node (ref "U1") (pin "22") (pinfunction "PIO4_22") (pintype "bidirectional"))
    )
    (net (code "77") (name "Net-(U1-PIO5)") (class "Default")
      (node (ref "LED2") (pin "A") (pinfunction "A_A") (pintype "passive"))
      (node (ref "U1") (pin "21") (pinfunction "PIO5_21") (pintype "bidirectional"))
    )
    (net (code "78") (name "Net-(U5-RF_ANT)") (class "Default")
      (node (ref "C17") (pin "2") (pinfunction "2_2") (pintype "passive"))
      (node (ref "U5") (pin "P$35") (pinfunction "RF_ANT_P$35") (pintype "bidirectional"))
    )
    (net (code "79") (name "Net-(U5-SCL_CC3000)") (class "Default")
      (node (ref "U5") (pin "P$29") (pinfunction "SCL_EEPROM_P$29") (pintype "bidirectional"))
      (node (ref "U5") (pin "P$30") (pinfunction "SCL_CC3000_P$30") (pintype "bidirectional"))
    )
    (net (code "80") (name "Net-(U5-SDA_CC3000)") (class "Default")
      (node (ref "U5") (pin "P$27") (pinfunction "SDA_EEPROM_P$27") (pintype "bidirectional"))
      (node (ref "U5") (pin "P$28") (pinfunction "SDA_CC3000_P$28") (pintype "bidirectional"))
    )
    (net (code "81") (name "Net-(U5-WL_EN1)") (class "Default")
      (node (ref "SJ1") (pin "1") (pinfunction "1_1") (pintype "passive"))
      (node (ref "U5") (pin "P$7") (pinfunction "WL_EN1_P$7") (pintype "bidirectional"))
    )
    (net (code "82") (name "Net-(U5-WL_EN2)") (class "Default")
      (node (ref "SJ1") (pin "2") (pinfunction "2_2") (pintype "passive"))
      (node (ref "U5") (pin "P$5") (pinfunction "WL_EN2_P$5") (pintype "bidirectional"))
    )
    (net (code "83") (name "Net-(U6-AREF)") (class "Default")
      (node (ref "C23") (pin "1") (pinfunction "1_1") (pintype "passive"))
      (node (ref "U6") (pin "20") (pinfunction "AREF_20") (pintype "bidirectional"))
    )
    (net (code "84") (name "RX") (class "Default")
      (node (ref "U1") (pin "13") (pinfunction "UARTRX_13") (pintype "bidirectional"))
      (node (ref "U3") (pin "15") (pinfunction "6Y_15") (pintype "bidirectional"))
    )
    (net (code "85") (name "SCK_3.3V") (class "Default")
      (node (ref "U3") (pin "4") (pinfunction "2Y_4") (pintype "bidirectional"))
      (node (ref "U5") (pin "P$17") (pinfunction "SPI_CLK_P$17") (pintype "bidirectional"))
    )
    (net (code "86") (name "SCK_5V") (class "Default")
      (node (ref "U3") (pin "5") (pinfunction "2A_5") (pintype "bidirectional"))
    )
    (net (code "87") (name "TX") (class "Default")
      (node (ref "U1") (pin "14") (pinfunction "UARTTX_14") (pintype "bidirectional"))
      (node (ref "U3") (pin "10") (pinfunction "4Y_10") (pintype "bidirectional"))
    )
    (net (code "88") (name "WIFI_RX") (class "Default")
      (node (ref "U5") (pin "P$8") (pinfunction "WL_RS232_RX_P$8") (pintype "bidirectional"))
    )
    (net (code "89") (name "WIFI_TX") (class "Default")
      (node (ref "U5") (pin "P$6") (pinfunction "WL_RS232_TX_P$6") (pintype "bidirectional"))
    )
    (net (code "90") (name "unconnected-(U$11-NC-Pad13)") (class "Default")
      (node (ref "U$11") (pin "13") (pinfunction "NC_13") (pintype "no_connect"))
    )
    (net (code "91") (name "unconnected-(U1-AIO1-Pad35)") (class "Default")
      (node (ref "U1") (pin "35") (pinfunction "AIO1_35") (pintype "bidirectional"))
    )
    (net (code "92") (name "unconnected-(U1-AIO2-Pad30)") (class "Default")
      (node (ref "U1") (pin "30") (pinfunction "AIO2_30") (pintype "bidirectional"))
    )
    (net (code "93") (name "unconnected-(U1-NC-Pad26)") (class "Default")
      (node (ref "U1") (pin "26") (pinfunction "NC_26") (pintype "bidirectional"))
    )
    (net (code "94") (name "unconnected-(U1-PCMCLK-Pad7)") (class "Default")
      (node (ref "U1") (pin "7") (pinfunction "PCMCLK_7") (pintype "bidirectional"))
    )
    (net (code "95") (name "unconnected-(U1-PCMIN-Pad9)") (class "Default")
      (node (ref "U1") (pin "9") (pinfunction "PCMIN_9") (pintype "bidirectional"))
    )
    (net (code "96") (name "unconnected-(U1-PCMOUT-Pad10)") (class "Default")
      (node (ref "U1") (pin "10") (pinfunction "PCMOUT_10") (pintype "bidirectional"))
    )
    (net (code "97") (name "unconnected-(U1-PCMSYNC-Pad8)") (class "Default")
      (node (ref "U1") (pin "8") (pinfunction "PCMSYNC_8") (pintype "bidirectional"))
    )
    (net (code "98") (name "unconnected-(U1-PIO3-Pad20)") (class "Default")
      (node (ref "U1") (pin "20") (pinfunction "PIO3_20") (pintype "bidirectional"))
    )
    (net (code "99") (name "unconnected-(U1-PIO6-Pad3)") (class "Default")
      (node (ref "U1") (pin "3") (pinfunction "PIO6_3") (pintype "bidirectional"))
    )
    (net (code "100") (name "unconnected-(U1-PIO7-Pad4)") (class "Default")
      (node (ref "U1") (pin "4") (pinfunction "PIO7_4") (pintype "bidirectional"))
    )
    (net (code "101") (name "unconnected-(U1-PIO8-Pad31)") (class "Default")
      (node (ref "U1") (pin "31") (pinfunction "PIO8_31") (pintype "bidirectional"))
    )
    (net (code "102") (name "unconnected-(U1-PIO9-Pad32)") (class "Default")
      (node (ref "U1") (pin "32") (pinfunction "PIO9_32") (pintype "bidirectional"))
    )
    (net (code "103") (name "unconnected-(U1-PIO10-Pad33)") (class "Default")
      (node (ref "U1") (pin "33") (pinfunction "PIO10_33") (pintype "bidirectional"))
    )
    (net (code "104") (name "unconnected-(U1-PIO11-Pad34)") (class "Default")
      (node (ref "U1") (pin "34") (pinfunction "PIO11_34") (pintype "bidirectional"))
    )
    (net (code "105") (name "unconnected-(U1-RESET-Pad5)") (class "Default")
      (node (ref "U1") (pin "5") (pinfunction "RESET_5") (pintype "bidirectional"))
    )
    (net (code "106") (name "unconnected-(U1-SPICLK-Pad6)") (class "Default")
      (node (ref "U1") (pin "6") (pinfunction "SPICLK_6") (pintype "bidirectional"))
    )
    (net (code "107") (name "unconnected-(U1-SPICSB-Pad23)") (class "Default")
      (node (ref "U1") (pin "23") (pinfunction "SPICSB_23") (pintype "bidirectional"))
    )
    (net (code "108") (name "unconnected-(U1-SPIMISO-Pad24)") (class "Default")
      (node (ref "U1") (pin "24") (pinfunction "SPIMISO_24") (pintype "bidirectional"))
    )
    (net (code "109") (name "unconnected-(U1-SPIMOSI-Pad2)") (class "Default")
      (node (ref "U1") (pin "2") (pinfunction "SPIMOSI_2") (pintype "bidirectional"))
    )
    (net (code "110") (name "unconnected-(U1-USBD+-Pad17)") (class "Default")
      (node (ref "U1") (pin "17") (pinfunction "USBD+_17") (pintype "bidirectional"))
    )
    (net (code "111") (name "unconnected-(U1-USBD--Pad18)") (class "Default")
      (node (ref "U1") (pin "18") (pinfunction "USBD-_18") (pintype "bidirectional"))
    )
    (net (code "112") (name "unconnected-(U5-NC-PadP$3)") (class "Default")
      (node (ref "U5") (pin "P$3") (pinfunction "NC_P$3") (pintype "bidirectional"))
    )
    (net (code "113") (name "unconnected-(U5-RESERVED_1-PadP$2)") (class "Default")
      (node (ref "U5") (pin "P$2") (pinfunction "RESERVED_1_P$2") (pintype "bidirectional"))
    )
    (net (code "114") (name "unconnected-(U5-RESERVED_2-PadP$4)") (class "Default")
      (node (ref "U5") (pin "P$4") (pinfunction "RESERVED_2_P$4") (pintype "bidirectional"))
    )
    (net (code "115") (name "unconnected-(U5-RESERVED_3-PadP$24)") (class "Default")
      (node (ref "U5") (pin "P$24") (pinfunction "RESERVED_3_P$24") (pintype "bidirectional"))
    )
  )
)
